# schematic-easyeda.net
KiCad netlist of a schematic drawn in EasyEDA
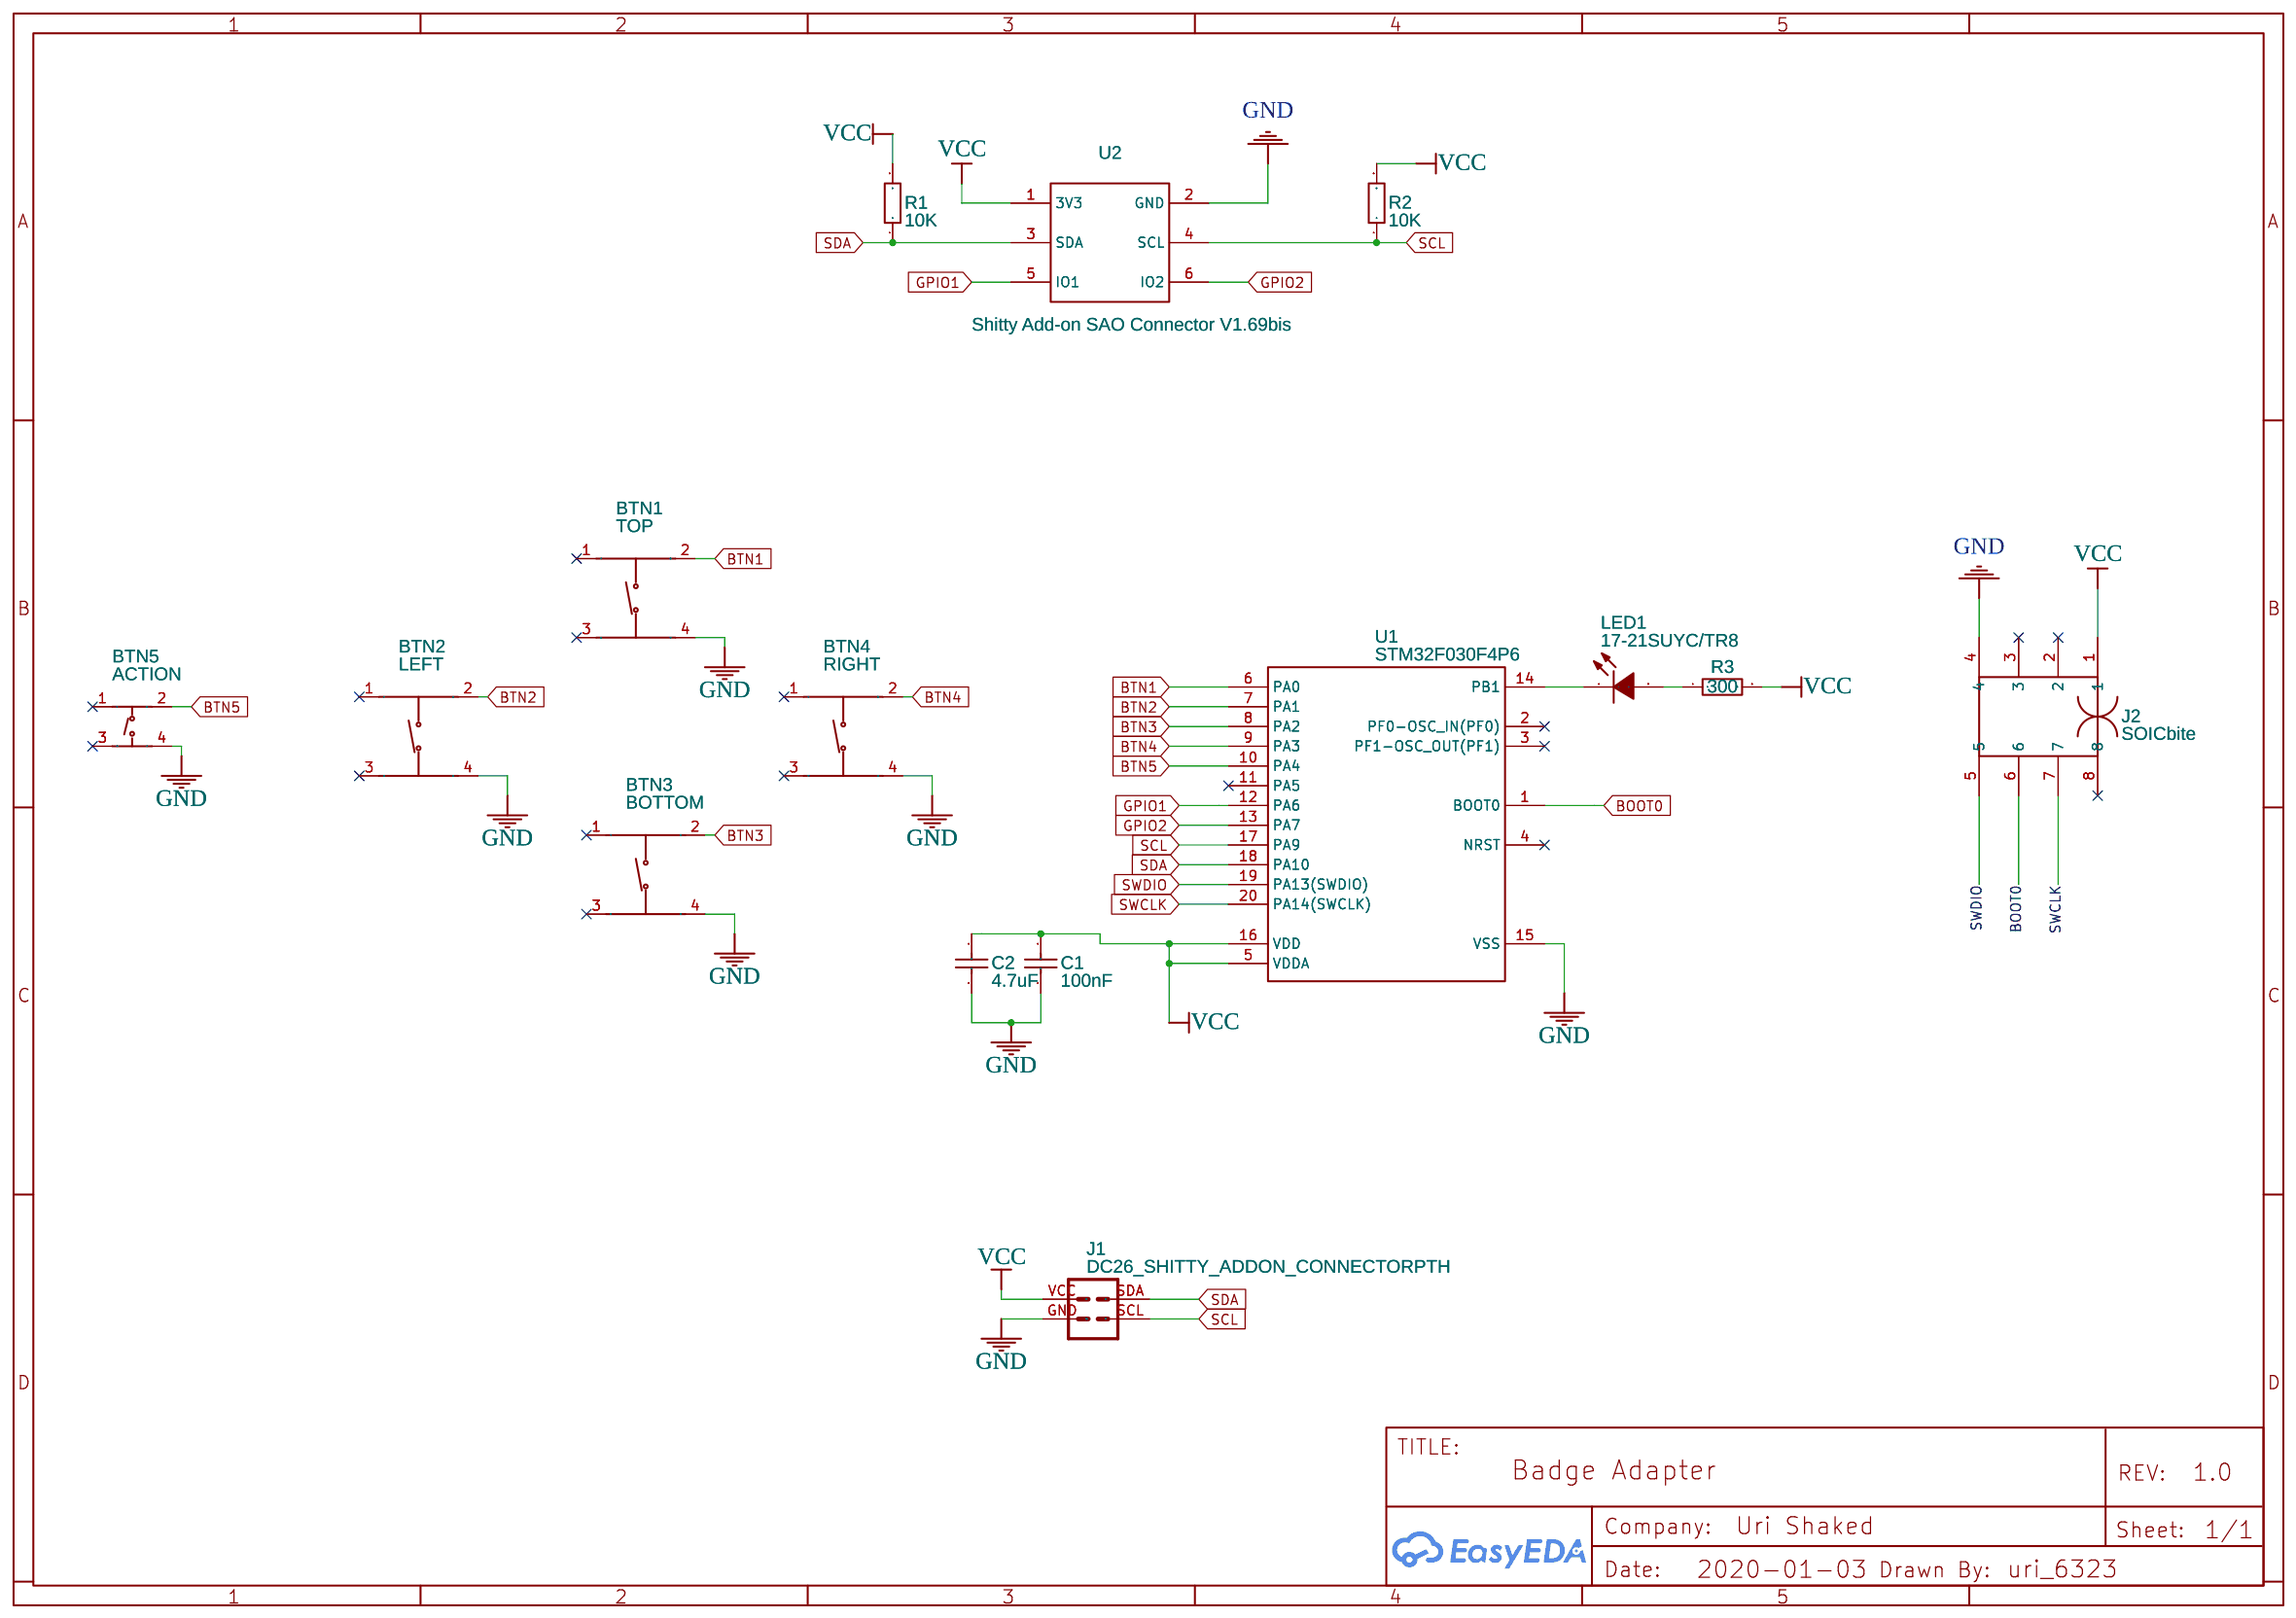
[diagram p0: schematic sheet]

(export (version "E")
  (design (tool "Eeschema 10.0.6"))
  (components
    (comp (ref "BTN1")
      (value "TOP")
      (fields
        (field (name "BOM_Manufacturer Part") "TC-1102T-C")
        (field (name "BOM_Supplier Part") "C406163")
      )
      (libsource (lib "") (part "TC-1102T-C"))
    )
    (comp (ref "BTN2")
      (value "LEFT")
      (fields
        (field (name "BOM_Manufacturer Part") "TC-1102T-C")
        (field (name "BOM_Supplier Part") "C406163")
      )
      (libsource (lib "") (part "TC-1102T-C"))
    )
    (comp (ref "BTN3")
      (value "BOTTOM")
      (fields
        (field (name "BOM_Manufacturer Part") "TC-1102T-C")
        (field (name "BOM_Supplier Part") "C406163")
      )
      (libsource (lib "") (part "TC-1102T-C"))
    )
    (comp (ref "BTN4")
      (value "RIGHT")
      (fields
        (field (name "BOM_Manufacturer Part") "TC-1102T-C")
        (field (name "BOM_Supplier Part") "C406163")
      )
      (libsource (lib "") (part "TC-1102T-C"))
    )
    (comp (ref "BTN5")
      (value "ACTION")
      (fields
        (field (name "BOM_Manufacturer Part") "1TS005A-2400-5001")
        (field (name "BOM_Supplier Part") "C319406")
      )
      (libsource (lib "") (part "1TS005A-2400-5001"))
    )
    (comp (ref "C1")
      (value "100nF")
      (fields
        (field (name "BOM_Manufacturer Part") "CL31B104KBCNNNC")
        (field (name "BOM_Supplier Part") "C24497")
      )
      (libsource (lib "") (part "CL31B104KBCNNNC"))
    )
    (comp (ref "C2")
      (value "4.7uF")
      (fields
        (field (name "BOM_Manufacturer Part") "1206B475K500NT")
        (field (name "BOM_Supplier Part") "C29823")
      )
      (libsource (lib "") (part "1206B475K500NT"))
    )
    (comp (ref "J1") (value "DC26_SHITTY_ADDON_CONNECTORPTH") (libsource (lib "") (part "Unknown_555_-145")))
    (comp (ref "J2") (value "SOICbite") (libsource (lib "") (part "Unknown_1015_-440")))
    (comp (ref "LED1")
      (value "17-21SUYC/TR8")
      (fields (field (name "BOM_Supplier Part") "C2296"))
      (libsource (lib "") (part "17-21SUYC/TR8"))
    )
    (comp (ref "R1")
      (value "10K")
      (fields
        (field (name "BOM_Manufacturer Part") "1206W4F1002T5E")
        (field (name "BOM_Supplier Part") "C17902")
      )
      (libsource (lib "") (part "1206W4F1002T5E"))
    )
    (comp (ref "R2")
      (value "10K")
      (fields
        (field (name "BOM_Manufacturer Part") "1206W4F1002T5E")
        (field (name "BOM_Supplier Part") "C17902")
      )
      (libsource (lib "") (part "1206W4F1002T5E"))
    )
    (comp (ref "R3")
      (value "300")
      (fields
        (field (name "BOM_Manufacturer Part") "1206W4F3000T5E")
        (field (name "BOM_Supplier Part") "C17887")
      )
      (libsource (lib "") (part "1206W4F3000T5E"))
    )
    (comp (ref "U1")
      (value "STM32F030F4P6")
      (fields (field (name "BOM_Supplier Part") "C32908"))
      (libsource (lib "") (part "STM32F030F4P6"))
    )
    (comp (ref "U2")
      (value "Shitty Add-on SAO Connector V1.69bis")
      (libsource (lib "") (part "Shitty Add-on SAO Connector V1.69bis"))
    )
  )
  (nets
    (net (code "1") (name "BOOT0") (class "Default")
      (node (ref "J2") (pin "6") (pinfunction "6_6") (pintype "unspecified"))
      (node (ref "U1") (pin "1") (pinfunction "BOOT0_1") (pintype "unspecified"))
    )
    (net (code "2") (name "BTN1") (class "Default")
      (node (ref "BTN1") (pin "2") (pinfunction "B_2") (pintype "unspecified"))
      (node (ref "U1") (pin "6") (pinfunction "PA0_6") (pintype "bidirectional"))
    )
    (net (code "3") (name "BTN2") (class "Default")
      (node (ref "BTN2") (pin "2") (pinfunction "B_2") (pintype "unspecified"))
      (node (ref "U1") (pin "7") (pinfunction "PA1_7") (pintype "bidirectional"))
    )
    (net (code "4") (name "BTN3") (class "Default")
      (node (ref "BTN3") (pin "2") (pinfunction "B_2") (pintype "unspecified"))
      (node (ref "U1") (pin "8") (pinfunction "PA2_8") (pintype "bidirectional"))
    )
    (net (code "5") (name "BTN4") (class "Default")
      (node (ref "BTN4") (pin "2") (pinfunction "B_2") (pintype "unspecified"))
      (node (ref "U1") (pin "9") (pinfunction "PA3_9") (pintype "bidirectional"))
    )
    (net (code "6") (name "BTN5") (class "Default")
      (node (ref "BTN5") (pin "2") (pinfunction "2_2") (pintype "unspecified"))
      (node (ref "U1") (pin "10") (pinfunction "PA4_10") (pintype "bidirectional"))
    )
    (net (code "7") (name "GND") (class "Default")
      (node (ref "BTN1") (pin "4") (pinfunction "D_4") (pintype "unspecified"))
      (node (ref "BTN2") (pin "4") (pinfunction "D_4") (pintype "unspecified"))
      (node (ref "BTN3") (pin "4") (pinfunction "D_4") (pintype "unspecified"))
      (node (ref "BTN4") (pin "4") (pinfunction "D_4") (pintype "unspecified"))
      (node (ref "BTN5") (pin "4") (pinfunction "4_4") (pintype "unspecified"))
      (node (ref "C1") (pin "1") (pinfunction "1_1") (pintype "input"))
      (node (ref "C2") (pin "1") (pinfunction "1_1") (pintype "input"))
      (node (ref "J1") (pin "GND") (pinfunction "GND_GND") (pintype "bidirectional"))
      (node (ref "J2") (pin "4") (pinfunction "4_4") (pintype "unspecified"))
      (node (ref "U1") (pin "15") (pinfunction "VSS_15") (pintype "passive"))
      (node (ref "U2") (pin "2") (pinfunction "GND_2") (pintype "unspecified"))
    )
    (net (code "8") (name "GPIO1") (class "Default")
      (node (ref "U1") (pin "12") (pinfunction "PA6_12") (pintype "bidirectional"))
      (node (ref "U2") (pin "5") (pinfunction "IO1_5") (pintype "unspecified"))
    )
    (net (code "9") (name "GPIO2") (class "Default")
      (node (ref "U1") (pin "13") (pinfunction "PA7_13") (pintype "bidirectional"))
      (node (ref "U2") (pin "6") (pinfunction "IO2_6") (pintype "unspecified"))
    )
    (net (code "10") (name "Net-(LED1-+)") (class "Default")
      (node (ref "LED1") (pin "2") (pinfunction "+_2") (pintype "unspecified"))
      (node (ref "R3") (pin "1") (pinfunction "1_1") (pintype "input"))
    )
    (net (code "11") (name "Net-(LED1--)") (class "Default")
      (node (ref "LED1") (pin "1") (pinfunction "-_1") (pintype "unspecified"))
      (node (ref "U1") (pin "14") (pinfunction "PB1_14") (pintype "bidirectional"))
    )
    (net (code "12") (name "SCL") (class "Default")
      (node (ref "J1") (pin "SCL") (pinfunction "SCL_SCL") (pintype "bidirectional"))
      (node (ref "R2") (pin "1") (pinfunction "1_1") (pintype "input"))
      (node (ref "U1") (pin "17") (pinfunction "PA9_17") (pintype "bidirectional"))
      (node (ref "U2") (pin "4") (pinfunction "SCL_4") (pintype "unspecified"))
    )
    (net (code "13") (name "SDA") (class "Default")
      (node (ref "J1") (pin "SDA") (pinfunction "SDA_SDA") (pintype "bidirectional"))
      (node (ref "R1") (pin "1") (pinfunction "1_1") (pintype "input"))
      (node (ref "U1") (pin "18") (pinfunction "PA10_18") (pintype "bidirectional"))
      (node (ref "U2") (pin "3") (pinfunction "SDA_3") (pintype "unspecified"))
    )
    (net (code "14") (name "SWCLK") (class "Default")
      (node (ref "J2") (pin "7") (pinfunction "7_7") (pintype "unspecified"))
      (node (ref "U1") (pin "20") (pinfunction "PA14(SWCLK)_20") (pintype "bidirectional"))
    )
    (net (code "15") (name "SWDIO") (class "Default")
      (node (ref "J2") (pin "5") (pinfunction "5_5") (pintype "unspecified"))
      (node (ref "U1") (pin "19") (pinfunction "PA13(SWDIO)_19") (pintype "bidirectional"))
    )
    (net (code "16") (name "VCC") (class "Default")
      (node (ref "C1") (pin "2") (pinfunction "2_2") (pintype "input"))
      (node (ref "C2") (pin "2") (pinfunction "2_2") (pintype "input"))
      (node (ref "J1") (pin "VCC") (pinfunction "VCC_VCC") (pintype "bidirectional"))
      (node (ref "J2") (pin "1") (pinfunction "1_1") (pintype "unspecified"))
      (node (ref "R1") (pin "2") (pinfunction "2_2") (pintype "input"))
      (node (ref "R2") (pin "2") (pinfunction "2_2") (pintype "input"))
      (node (ref "R3") (pin "2") (pinfunction "2_2") (pintype "input"))
      (node (ref "U1") (pin "16") (pinfunction "VDD_16") (pintype "passive"))
      (node (ref "U1") (pin "5") (pinfunction "VDDA_5") (pintype "passive"))
      (node (ref "U2") (pin "1") (pinfunction "3V3_1") (pintype "unspecified"))
    )
    (net (code "17") (name "unconnected-(BTN1-A-Pad1)") (class "Default")
      (node (ref "BTN1") (pin "1") (pinfunction "A_1") (pintype "unspecified+no_connect"))
    )
    (net (code "18") (name "unconnected-(BTN1-C-Pad3)") (class "Default")
      (node (ref "BTN1") (pin "3") (pinfunction "C_3") (pintype "unspecified+no_connect"))
    )
    (net (code "19") (name "unconnected-(BTN2-A-Pad1)") (class "Default")
      (node (ref "BTN2") (pin "1") (pinfunction "A_1") (pintype "unspecified+no_connect"))
    )
    (net (code "20") (name "unconnected-(BTN2-C-Pad3)") (class "Default")
      (node (ref "BTN2") (pin "3") (pinfunction "C_3") (pintype "unspecified+no_connect"))
    )
    (net (code "21") (name "unconnected-(BTN3-A-Pad1)") (class "Default")
      (node (ref "BTN3") (pin "1") (pinfunction "A_1") (pintype "unspecified+no_connect"))
    )
    (net (code "22") (name "unconnected-(BTN3-C-Pad3)") (class "Default")
      (node (ref "BTN3") (pin "3") (pinfunction "C_3") (pintype "unspecified+no_connect"))
    )
    (net (code "23") (name "unconnected-(BTN4-A-Pad1)") (class "Default")
      (node (ref "BTN4") (pin "1") (pinfunction "A_1") (pintype "unspecified+no_connect"))
    )
    (net (code "24") (name "unconnected-(BTN4-C-Pad3)") (class "Default")
      (node (ref "BTN4") (pin "3") (pinfunction "C_3") (pintype "unspecified+no_connect"))
    )
    (net (code "25") (name "unconnected-(BTN5-Pad1)") (class "Default")
      (node (ref "BTN5") (pin "1") (pinfunction "1_1") (pintype "unspecified+no_connect"))
    )
    (net (code "26") (name "unconnected-(BTN5-Pad3)") (class "Default")
      (node (ref "BTN5") (pin "3") (pinfunction "3_3") (pintype "unspecified+no_connect"))
    )
    (net (code "27") (name "unconnected-(J2-Pad2)") (class "Default")
      (node (ref "J2") (pin "2") (pinfunction "2_2") (pintype "unspecified+no_connect"))
    )
    (net (code "28") (name "unconnected-(J2-Pad3)") (class "Default")
      (node (ref "J2") (pin "3") (pinfunction "3_3") (pintype "unspecified+no_connect"))
    )
    (net (code "29") (name "unconnected-(J2-Pad8)") (class "Default")
      (node (ref "J2") (pin "8") (pinfunction "8_8") (pintype "unspecified+no_connect"))
    )
    (net (code "30") (name "unconnected-(U1-NRST-Pad4)") (class "Default")
      (node (ref "U1") (pin "4") (pinfunction "NRST_4") (pintype "bidirectional+no_connect"))
    )
    (net (code "31") (name "unconnected-(U1-PA5-Pad11)") (class "Default")
      (node (ref "U1") (pin "11") (pinfunction "PA5_11") (pintype "bidirectional+no_connect"))
    )
    (net (code "32") (name "unconnected-(U1-PF0-OSC_IN(PF0)-Pad2)") (class "Default")
      (node (ref "U1") (pin "2") (pinfunction "PF0-OSC_IN(PF0)_2") (pintype "bidirectional+no_connect"))
    )
    (net (code "33") (name "unconnected-(U1-PF1-OSC_OUT(PF1)-Pad3)") (class "Default")
      (node (ref "U1") (pin "3") (pinfunction "PF1-OSC_OUT(PF1)_3") (pintype "bidirectional+no_connect"))
    )
  )
)
